# ADS_PIC.net
KiCad netlist of a schematic drawn in Altium Designer
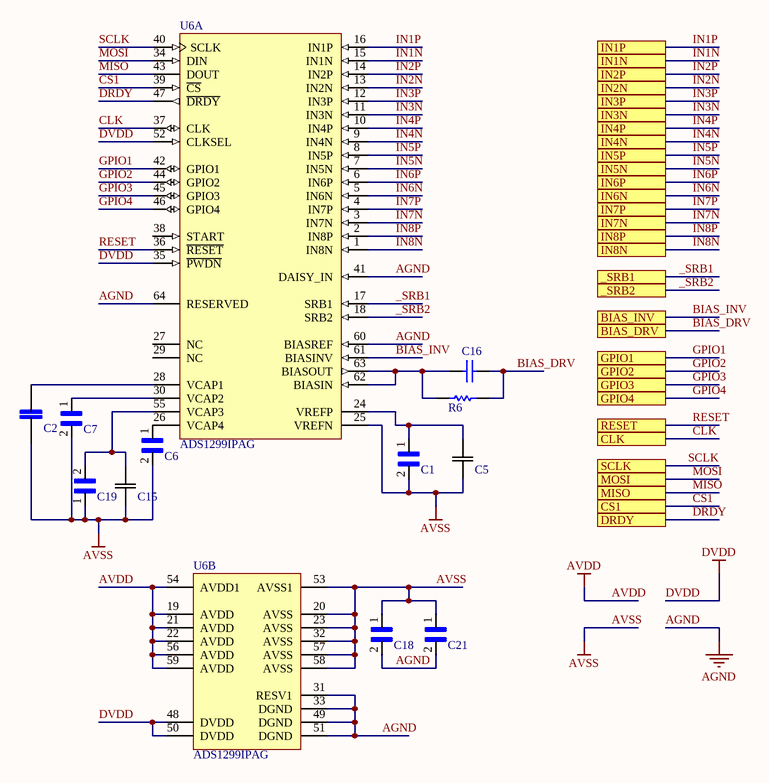
[diagram p0: ADS_PIC.SchDoc]

(export (version "E")
  (design (tool "Eeschema 10.0.6"))
  (components
    (comp (ref "C1")
      (value "GRM188C80G106KE47D")
      (footprint "*CAPC1608X90N")
      (description "CAP CER 10UF 4V X6S 0603")
      (fields (field (name "TOLERANCE") "10%"))
      (libsource (lib "EE_smallOB_BW_v1.0") (part "GRM188C80G106KE47D"))
    )
    (comp (ref "C2")
      (value "GRM31CR60J107ME39K")
      (description "MURATA - GRM31CR60J107ME39K - COND, 100µF, 6.3V, 20%, X5R, 1206")
      (fields (field (name "TOLERANCE") "20%") (field (name "VOLTAGE") "6.3V"))
      (libsource (lib "EE_smallOB_BW_v1.0") (part "GRM31CR60J107ME39K"))
    )
    (comp (ref "C5")
      (value "CC0402KRX7R7BB104")
      (footprint "YAG_CC0402")
      (description "CAP CER 0.1UF 16V X7R 0402")
      (fields (field (name "TOLERANCE") "10%") (field (name "VOLTAGE") "16V"))
      (libsource (lib "EE_smallOB_BW_v1.0") (part "CC0402KRX7R7BB104"))
    )
    (comp (ref "C6")
      (value "GRM155R70J105KA12J")
      (footprint "*CAPC1005X55N")
      (description "CAP CER 1UF 6.3V X7R 0402")
      (fields (field (name "TOLERANCE") "10%"))
      (libsource (lib "EE_smallOB_BW_v1.0") (part "GRM155R70J105KA12J"))
    )
    (comp (ref "C7")
      (value "GRM155R70J105KA12J")
      (footprint "*CAPC1005X55N")
      (description "CAP CER 1UF 6.3V X7R 0402")
      (fields (field (name "TOLERANCE") "10%"))
      (libsource (lib "EE_smallOB_BW_v1.0") (part "GRM155R70J105KA12J"))
    )
    (comp (ref "C15")
      (value "CC0402KRX7R7BB104")
      (footprint "YAG_CC0402")
      (description "CAP CER 0.1UF 16V X7R 0402")
      (fields (field (name "TOLERANCE") "10%") (field (name "VOLTAGE") "16V"))
      (libsource (lib "EE_smallOB_BW_v1.0") (part "CC0402KRX7R7BB104"))
    )
    (comp (ref "C16")
      (value "CC0402KRX7R7BB102")
      (description "CAP CER 1000PF 16V X7R 0402")
      (fields (field (name "TOLERANCE") "10%"))
      (libsource (lib "EE_smallOB_BW_v1.0") (part "CC0402KRX7R7BB102"))
    )
    (comp (ref "C18")
      (value "GRM155R70J105KA12J")
      (footprint "*CAPC1005X55N")
      (description "CAP CER 1UF 6.3V X7R 0402")
      (fields (field (name "TOLERANCE") "10%"))
      (libsource (lib "EE_smallOB_BW_v1.0") (part "GRM155R70J105KA12J"))
    )
    (comp (ref "C19")
      (value "GRM155R70J105KA12J")
      (footprint "*CAPC1005X55N")
      (description "CAP CER 1UF 6.3V X7R 0402")
      (fields (field (name "TOLERANCE") "10%"))
      (libsource (lib "EE_smallOB_BW_v1.0") (part "GRM155R70J105KA12J"))
    )
    (comp (ref "C21")
      (value "GRM155R70J105KA12J")
      (footprint "*CAPC1005X55N")
      (description "CAP CER 1UF 6.3V X7R 0402")
      (fields (field (name "TOLERANCE") "10%"))
      (libsource (lib "EE_smallOB_BW_v1.0") (part "GRM155R70J105KA12J"))
    )
    (comp (ref "R6")
      (value "RC0402JR-071ML")
      (description "RES SMD 1M OHM 5% 1/16W 0402")
      (fields (field (name "TOLERANCE") "5%"))
      (libsource (lib "EE_smallOB_BW_v1.0") (part "RC0402JR-071ML"))
    )
    (comp (ref "U6")
      (value "ADS1299IPAG")
      (footprint "PAG0064A_N")
      (description "IC AFE 24BIT 16KSPS LN 64TQFP")
      (libsource (lib "EE_smallOB_BW_v1.0") (part "ADS1299IPAG"))
    )
  )
  (nets
    (net (code "1") (name "/BIAS_DRV") (class "Default")
      (node (ref "C16") (pin "2") (pinfunction "2_2") (pintype "passive"))
      (node (ref "R6") (pin "2") (pinfunction "2_2") (pintype "passive"))
    )
    (net (code "2") (name "/BIAS_INV") (class "Default")
      (node (ref "U6") (pin "61") (pinfunction "BIASINV_61") (pintype "input"))
    )
    (net (code "3") (name "/CLK") (class "Default")
      (node (ref "U6") (pin "37") (pinfunction "CLK_37") (pintype "bidirectional"))
    )
    (net (code "4") (name "/CS1") (class "Default")
      (node (ref "U6") (pin "39") (pinfunction "~{CS}_39") (pintype "input"))
    )
    (net (code "5") (name "/DRDY") (class "Default")
      (node (ref "U6") (pin "47") (pinfunction "~{DRDY}_47") (pintype "output"))
    )
    (net (code "6") (name "/GPIO1") (class "Default")
      (node (ref "U6") (pin "42") (pinfunction "GPIO1_42") (pintype "bidirectional"))
    )
    (net (code "7") (name "/GPIO2") (class "Default")
      (node (ref "U6") (pin "44") (pinfunction "GPIO2_44") (pintype "bidirectional"))
    )
    (net (code "8") (name "/GPIO3") (class "Default")
      (node (ref "U6") (pin "45") (pinfunction "GPIO3_45") (pintype "bidirectional"))
    )
    (net (code "9") (name "/GPIO4") (class "Default")
      (node (ref "U6") (pin "46") (pinfunction "GPIO4_46") (pintype "bidirectional"))
    )
    (net (code "10") (name "/IN1N") (class "Default")
      (node (ref "U6") (pin "15") (pinfunction "IN1N_15") (pintype "input"))
    )
    (net (code "11") (name "/IN1P") (class "Default")
      (node (ref "U6") (pin "16") (pinfunction "IN1P_16") (pintype "input"))
    )
    (net (code "12") (name "/IN2N") (class "Default")
      (node (ref "U6") (pin "13") (pinfunction "IN2N_13") (pintype "input"))
    )
    (net (code "13") (name "/IN2P") (class "Default")
      (node (ref "U6") (pin "14") (pinfunction "IN2P_14") (pintype "input"))
    )
    (net (code "14") (name "/IN3N") (class "Default")
      (node (ref "U6") (pin "11") (pinfunction "IN3N_11") (pintype "input"))
    )
    (net (code "15") (name "/IN3P") (class "Default")
      (node (ref "U6") (pin "12") (pinfunction "IN3P_12") (pintype "input"))
    )
    (net (code "16") (name "/IN4N") (class "Default")
      (node (ref "U6") (pin "9") (pinfunction "IN4N_9") (pintype "input"))
    )
    (net (code "17") (name "/IN4P") (class "Default")
      (node (ref "U6") (pin "10") (pinfunction "IN4P_10") (pintype "input"))
    )
    (net (code "18") (name "/IN5N") (class "Default")
      (node (ref "U6") (pin "7") (pinfunction "IN5N_7") (pintype "input"))
    )
    (net (code "19") (name "/IN5P") (class "Default")
      (node (ref "U6") (pin "8") (pinfunction "IN5P_8") (pintype "input"))
    )
    (net (code "20") (name "/IN6N") (class "Default")
      (node (ref "U6") (pin "5") (pinfunction "IN6N_5") (pintype "input"))
    )
    (net (code "21") (name "/IN6P") (class "Default")
      (node (ref "U6") (pin "6") (pinfunction "IN6P_6") (pintype "input"))
    )
    (net (code "22") (name "/IN7N") (class "Default")
      (node (ref "U6") (pin "3") (pinfunction "IN7N_3") (pintype "input"))
    )
    (net (code "23") (name "/IN7P") (class "Default")
      (node (ref "U6") (pin "4") (pinfunction "IN7P_4") (pintype "input"))
    )
    (net (code "24") (name "/IN8N") (class "Default")
      (node (ref "U6") (pin "1") (pinfunction "IN8N_1") (pintype "input"))
    )
    (net (code "25") (name "/IN8P") (class "Default")
      (node (ref "U6") (pin "2") (pinfunction "IN8P_2") (pintype "input"))
    )
    (net (code "26") (name "/MISO") (class "Default")
      (node (ref "U6") (pin "43") (pinfunction "DOUT_43") (pintype "tri_state"))
    )
    (net (code "27") (name "/MOSI") (class "Default")
      (node (ref "U6") (pin "34") (pinfunction "DIN_34") (pintype "input"))
    )
    (net (code "28") (name "/RESET") (class "Default")
      (node (ref "U6") (pin "36") (pinfunction "~{RESET}_36") (pintype "input"))
    )
    (net (code "29") (name "/SCLK") (class "Default")
      (node (ref "U6") (pin "40") (pinfunction "SCLK_40") (pintype "input"))
    )
    (net (code "30") (name "/_SRB1") (class "Default")
      (node (ref "U6") (pin "17") (pinfunction "SRB1_17") (pintype "input"))
    )
    (net (code "31") (name "/_SRB2") (class "Default")
      (node (ref "U6") (pin "18") (pinfunction "SRB2_18") (pintype "input"))
    )
    (net (code "32") (name "AGND") (class "Default")
      (node (ref "C18") (pin "2") (pinfunction "2_2") (pintype "passive"))
      (node (ref "C21") (pin "2") (pinfunction "2_2") (pintype "passive"))
      (node (ref "U6") (pin "31") (pinfunction "RESV1_31") (pintype "power_in"))
      (node (ref "U6") (pin "33") (pinfunction "DGND_33") (pintype "power_in"))
      (node (ref "U6") (pin "41") (pinfunction "DAISY_IN_41") (pintype "input"))
      (node (ref "U6") (pin "49") (pinfunction "DGND_49") (pintype "power_in"))
      (node (ref "U6") (pin "51") (pinfunction "DGND_51") (pintype "power_in"))
      (node (ref "U6") (pin "60") (pinfunction "BIASREF_60") (pintype "input"))
      (node (ref "U6") (pin "64") (pinfunction "RESERVED_64") (pintype "passive"))
    )
    (net (code "33") (name "AVDD") (class "Default")
      (node (ref "U6") (pin "19") (pinfunction "AVDD_19") (pintype "power_in"))
      (node (ref "U6") (pin "21") (pinfunction "AVDD_21") (pintype "power_in"))
      (node (ref "U6") (pin "22") (pinfunction "AVDD_22") (pintype "power_in"))
      (node (ref "U6") (pin "54") (pinfunction "AVDD1_54") (pintype "power_in"))
      (node (ref "U6") (pin "56") (pinfunction "AVDD_56") (pintype "power_in"))
      (node (ref "U6") (pin "59") (pinfunction "AVDD_59") (pintype "power_in"))
    )
    (net (code "34") (name "AVSS") (class "Default")
      (node (ref "C1") (pin "2") (pinfunction "2_2") (pintype "passive"))
      (node (ref "C15") (pin "1") (pinfunction "1_1") (pintype "passive"))
      (node (ref "C18") (pin "1") (pinfunction "1_1") (pintype "passive"))
      (node (ref "C19") (pin "1") (pinfunction "1_1") (pintype "passive"))
      (node (ref "C2") (pin "2") (pinfunction "2_2") (pintype "passive"))
      (node (ref "C21") (pin "1") (pinfunction "1_1") (pintype "passive"))
      (node (ref "C5") (pin "2") (pinfunction "2_2") (pintype "passive"))
      (node (ref "C6") (pin "2") (pinfunction "2_2") (pintype "passive"))
      (node (ref "C7") (pin "2") (pinfunction "2_2") (pintype "passive"))
      (node (ref "U6") (pin "20") (pinfunction "AVSS_20") (pintype "power_in"))
      (node (ref "U6") (pin "23") (pinfunction "AVSS_23") (pintype "power_in"))
      (node (ref "U6") (pin "25") (pinfunction "VREFN_25") (pintype "passive"))
      (node (ref "U6") (pin "32") (pinfunction "AVSS_32") (pintype "power_in"))
      (node (ref "U6") (pin "53") (pinfunction "AVSS1_53") (pintype "power_in"))
      (node (ref "U6") (pin "57") (pinfunction "AVSS_57") (pintype "power_in"))
      (node (ref "U6") (pin "58") (pinfunction "AVSS_58") (pintype "power_in"))
    )
    (net (code "35") (name "DVDD") (class "Default")
      (node (ref "U6") (pin "35") (pinfunction "~{PWDN}_35") (pintype "input"))
      (node (ref "U6") (pin "48") (pinfunction "DVDD_48") (pintype "power_in"))
      (node (ref "U6") (pin "50") (pinfunction "DVDD_50") (pintype "power_in"))
      (node (ref "U6") (pin "52") (pinfunction "CLKSEL_52") (pintype "input"))
    )
    (net (code "36") (name "Net-(U6A-BIASIN)") (class "Default")
      (node (ref "C16") (pin "1") (pinfunction "1_1") (pintype "passive"))
      (node (ref "R6") (pin "1") (pinfunction "1_1") (pintype "passive"))
      (node (ref "U6") (pin "62") (pinfunction "BIASIN_62") (pintype "input"))
      (node (ref "U6") (pin "63") (pinfunction "BIASOUT_63") (pintype "output"))
    )
    (net (code "37") (name "Net-(U6A-VCAP1)") (class "Default")
      (node (ref "C2") (pin "1") (pinfunction "1_1") (pintype "passive"))
      (node (ref "U6") (pin "28") (pinfunction "VCAP1_28") (pintype "passive"))
    )
    (net (code "38") (name "Net-(U6A-VCAP2)") (class "Default")
      (node (ref "C7") (pin "1") (pinfunction "1_1") (pintype "passive"))
      (node (ref "U6") (pin "30") (pinfunction "VCAP2_30") (pintype "passive"))
    )
    (net (code "39") (name "Net-(U6A-VCAP3)") (class "Default")
      (node (ref "C15") (pin "2") (pinfunction "2_2") (pintype "passive"))
      (node (ref "C19") (pin "2") (pinfunction "2_2") (pintype "passive"))
      (node (ref "U6") (pin "55") (pinfunction "VCAP3_55") (pintype "passive"))
    )
    (net (code "40") (name "Net-(U6A-VCAP4)") (class "Default")
      (node (ref "C6") (pin "1") (pinfunction "1_1") (pintype "passive"))
      (node (ref "U6") (pin "26") (pinfunction "VCAP4_26") (pintype "passive"))
    )
    (net (code "41") (name "Net-(U6A-VREFP)") (class "Default")
      (node (ref "C1") (pin "1") (pinfunction "1_1") (pintype "passive"))
      (node (ref "C5") (pin "1") (pinfunction "1_1") (pintype "passive"))
      (node (ref "U6") (pin "24") (pinfunction "VREFP_24") (pintype "passive"))
    )
    (net (code "42") (name "unconnected-(U6A-NC-Pad27)") (class "Default")
      (node (ref "U6") (pin "27") (pinfunction "NC_27") (pintype "passive"))
    )
    (net (code "43") (name "unconnected-(U6A-NC-Pad29)") (class "Default")
      (node (ref "U6") (pin "29") (pinfunction "NC_29") (pintype "passive"))
    )
    (net (code "44") (name "unconnected-(U6A-START-Pad38)") (class "Default")
      (node (ref "U6") (pin "38") (pinfunction "START_38") (pintype "input"))
    )
  )
)
